# MUR_V0_1_Wiring.net
KiCad netlist of a schematic drawn in EAGLE
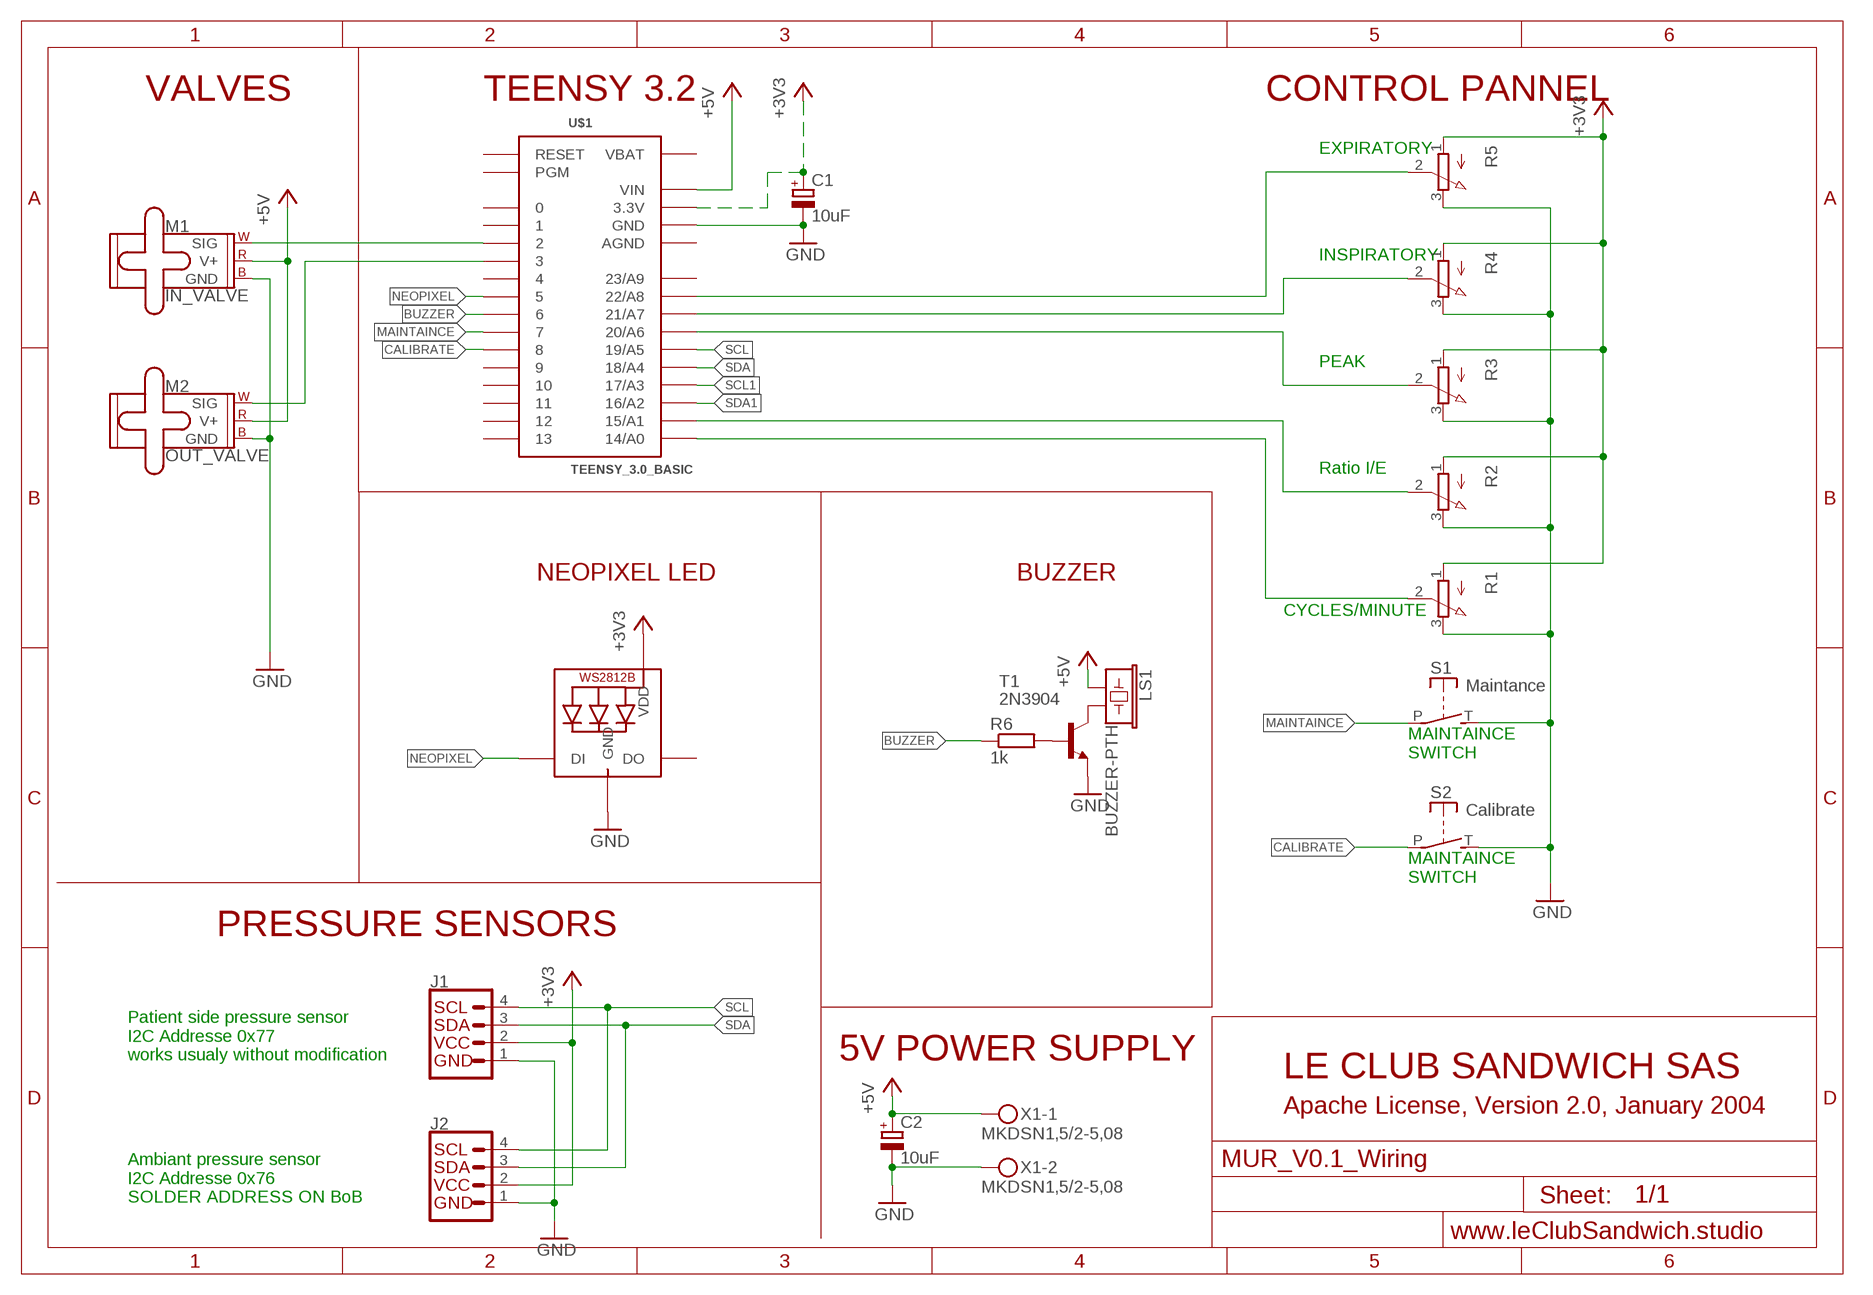
[diagram p0: schematic, sheet 1]

(export (version "E")
  (design (tool "Eeschema 10.0.6"))
  (components
    (comp (ref "C1")
      (value "10uF")
      (footprint "eagle-import:E2,5-6")
      (libsource (lib "eagle-import") (part "CPOL-EUE2.5-6"))
    )
    (comp (ref "C2")
      (value "10uF")
      (footprint "eagle-import:E2,5-6")
      (libsource (lib "eagle-import") (part "CPOL-EUE2.5-6"))
    )
    (comp (ref "J1")
      (value "I2C_STANDARD_NO_SILK")
      (footprint "eagle-import:1X04_NO_SILK")
      (libsource (lib "eagle-import") (part "I2C_STANDARD_NO_SILK"))
    )
    (comp (ref "J2")
      (value "I2C_STANDARD_NO_SILK")
      (footprint "eagle-import:1X04_NO_SILK")
      (libsource (lib "eagle-import") (part "I2C_STANDARD_NO_SILK"))
    )
    (comp (ref "LED1")
      (value "WS2812B5050")
      (footprint "eagle-import:WS2812B")
      (libsource (lib "eagle-import") (part "WS2812B5050"))
    )
    (comp (ref "LS1")
      (value "BUZZER-PTH")
      (footprint "eagle-import:BUZZER-12MM")
      (libsource (lib "eagle-import") (part "BUZZER-PTH"))
    )
    (comp (ref "M1")
      (value "IN_VALVE")
      (footprint "eagle-import:1X03")
      (libsource (lib "eagle-import") (part "SERVO"))
    )
    (comp (ref "M2")
      (value "OUT_VALVE")
      (footprint "eagle-import:1X03")
      (libsource (lib "eagle-import") (part "SERVO"))
    )
    (comp (ref "R1")
      (value "3RP/1610N")
      (footprint "eagle-import:3RP_1610N")
      (libsource (lib "eagle-import") (part "3RP/1610N"))
    )
    (comp (ref "R2")
      (value "3RP/1610N")
      (footprint "eagle-import:3RP_1610N")
      (libsource (lib "eagle-import") (part "3RP/1610N"))
    )
    (comp (ref "R3")
      (value "3RP/1610N")
      (footprint "eagle-import:3RP_1610N")
      (libsource (lib "eagle-import") (part "3RP/1610N"))
    )
    (comp (ref "R4")
      (value "3RP/1610N")
      (footprint "eagle-import:3RP_1610N")
      (libsource (lib "eagle-import") (part "3RP/1610N"))
    )
    (comp (ref "R5")
      (value "3RP/1610N")
      (footprint "eagle-import:3RP_1610N")
      (libsource (lib "eagle-import") (part "3RP/1610N"))
    )
    (comp (ref "R6")
      (value "1k")
      (footprint "eagle-import:0204_5")
      (libsource (lib "eagle-import") (part "R-EU_0204/5"))
    )
    (comp (ref "S1")
      (value "Maintance")
      (footprint "eagle-import:JUDCOSPST")
      (libsource (lib "eagle-import") (part "SPST"))
    )
    (comp (ref "S2")
      (value "Calibrate")
      (footprint "eagle-import:JUDCOSPST")
      (libsource (lib "eagle-import") (part "SPST"))
    )
    (comp (ref "T1")
      (value "2N3904")
      (footprint "eagle-import:TO92")
      (libsource (lib "eagle-import") (part "2N3904"))
    )
    (comp (ref "U$1")
      (value "TEENSY_3.0_BASIC")
      (footprint "eagle-import:TEENSY_3.0_BASIC")
      (libsource (lib "eagle-import") (part "TEENSY_3.0_BASIC"))
    )
    (comp (ref "X1")
      (value "MKDSN1,5/2-5,08")
      (footprint "eagle-import:MKDSN1,5_2-5,08")
      (libsource (lib "eagle-import") (part "MKDSN1,5/2-5,08"))
    )
  )
  (nets
    (net (code "1") (name "+3V3") (class "Default")
      (node (ref "C1") (pin "+") (pinfunction "+_+") (pintype "passive"))
      (node (ref "J1") (pin "2") (pinfunction "2_2") (pintype "power_in"))
      (node (ref "J2") (pin "2") (pinfunction "2_2") (pintype "power_in"))
      (node (ref "LED1") (pin "1-VDD") (pinfunction "VDD_1-VDD") (pintype "power_in"))
      (node (ref "R1") (pin "1") (pinfunction "A_1") (pintype "passive"))
      (node (ref "R2") (pin "1") (pinfunction "A_1") (pintype "passive"))
      (node (ref "R3") (pin "1") (pinfunction "A_1") (pintype "passive"))
      (node (ref "R4") (pin "1") (pinfunction "A_1") (pintype "passive"))
      (node (ref "R5") (pin "1") (pinfunction "A_1") (pintype "passive"))
      (node (ref "U$1") (pin "3.3V") (pinfunction "3.3V_3.3V") (pintype "power_in"))
      (node (ref "U$1") (pin "3.3V1") (pinfunction "3.3V_3.3V1") (pintype "power_in"))
    )
    (net (code "2") (name "+5V") (class "Default")
      (node (ref "C2") (pin "+") (pinfunction "+_+") (pintype "passive"))
      (node (ref "LS1") (pin "+") (pinfunction "1_+") (pintype "passive"))
      (node (ref "M1") (pin "2") (pinfunction "V+_2") (pintype "bidirectional"))
      (node (ref "M2") (pin "2") (pinfunction "V+_2") (pintype "bidirectional"))
      (node (ref "U$1") (pin "VIN") (pinfunction "VIN_VIN") (pintype "power_in"))
      (node (ref "X1") (pin "1") (pinfunction "KL_1") (pintype "passive"))
    )
    (net (code "3") (name "/AGND") (class "Default")
      (node (ref "U$1") (pin "AGND") (pinfunction "AGND_AGND") (pintype "power_in"))
    )
    (net (code "4") (name "/VBAT") (class "Default")
      (node (ref "U$1") (pin "VBAT") (pinfunction "VBAT_VBAT") (pintype "power_in"))
    )
    (net (code "5") (name "BUZZER") (class "Default")
      (node (ref "R6") (pin "1") (pinfunction "1_1") (pintype "passive"))
      (node (ref "U$1") (pin "6") (pinfunction "6_6") (pintype "bidirectional"))
    )
    (net (code "6") (name "CALIBRATE") (class "Default")
      (node (ref "S2") (pin "P") (pinfunction "P_P") (pintype "passive"))
      (node (ref "U$1") (pin "8") (pinfunction "8_8") (pintype "bidirectional"))
    )
    (net (code "7") (name "GND") (class "Default")
      (node (ref "C1") (pin "-") (pinfunction "-_-") (pintype "passive"))
      (node (ref "C2") (pin "-") (pinfunction "-_-") (pintype "passive"))
      (node (ref "J1") (pin "1") (pinfunction "1_1") (pintype "power_in"))
      (node (ref "J2") (pin "1") (pinfunction "1_1") (pintype "power_in"))
      (node (ref "LED1") (pin "3-GND") (pinfunction "GND_3-GND") (pintype "power_in"))
      (node (ref "M1") (pin "3") (pinfunction "GND_3") (pintype "bidirectional"))
      (node (ref "M2") (pin "3") (pinfunction "GND_3") (pintype "bidirectional"))
      (node (ref "R1") (pin "3") (pinfunction "E_3") (pintype "passive"))
      (node (ref "R2") (pin "3") (pinfunction "E_3") (pintype "passive"))
      (node (ref "R3") (pin "3") (pinfunction "E_3") (pintype "passive"))
      (node (ref "R4") (pin "3") (pinfunction "E_3") (pintype "passive"))
      (node (ref "R5") (pin "3") (pinfunction "E_3") (pintype "passive"))
      (node (ref "S1") (pin "T") (pinfunction "S_T") (pintype "passive"))
      (node (ref "S2") (pin "T") (pinfunction "S_T") (pintype "passive"))
      (node (ref "T1") (pin "3") (pinfunction "E_3") (pintype "passive"))
      (node (ref "U$1") (pin "GND") (pinfunction "GND_GND") (pintype "power_in"))
      (node (ref "U$1") (pin "GND1") (pinfunction "GND_GND1") (pintype "power_in"))
      (node (ref "X1") (pin "2") (pinfunction "KL_2") (pintype "passive"))
    )
    (net (code "8") (name "MAINTAINCE") (class "Default")
      (node (ref "S1") (pin "P") (pinfunction "P_P") (pintype "passive"))
      (node (ref "U$1") (pin "7") (pinfunction "7_7") (pintype "bidirectional"))
    )
    (net (code "9") (name "NEOPIXEL") (class "Default")
      (node (ref "LED1") (pin "4-DIN") (pinfunction "DI_4-DIN") (pintype "input"))
      (node (ref "U$1") (pin "5") (pinfunction "5_5") (pintype "bidirectional"))
    )
    (net (code "10") (name "Net-(LS1-2)") (class "Default")
      (node (ref "LS1") (pin "-") (pinfunction "2_-") (pintype "passive"))
      (node (ref "T1") (pin "1") (pinfunction "C_1") (pintype "passive"))
    )
    (net (code "11") (name "Net-(M1-SIG)") (class "Default")
      (node (ref "M1") (pin "1") (pinfunction "SIG_1") (pintype "bidirectional"))
      (node (ref "U$1") (pin "2") (pinfunction "2_2") (pintype "bidirectional"))
    )
    (net (code "12") (name "Net-(M2-SIG)") (class "Default")
      (node (ref "M2") (pin "1") (pinfunction "SIG_1") (pintype "bidirectional"))
      (node (ref "U$1") (pin "3") (pinfunction "3_3") (pintype "bidirectional"))
    )
    (net (code "13") (name "Net-(R1-S)") (class "Default")
      (node (ref "R1") (pin "2") (pinfunction "S_2") (pintype "passive"))
      (node (ref "U$1") (pin "14/A0") (pinfunction "14/A0_14/A0") (pintype "bidirectional"))
    )
    (net (code "14") (name "Net-(R2-S)") (class "Default")
      (node (ref "R2") (pin "2") (pinfunction "S_2") (pintype "passive"))
      (node (ref "U$1") (pin "15/A1") (pinfunction "15/A1_15/A1") (pintype "bidirectional"))
    )
    (net (code "15") (name "Net-(R3-S)") (class "Default")
      (node (ref "R3") (pin "2") (pinfunction "S_2") (pintype "passive"))
      (node (ref "U$1") (pin "20/A6") (pinfunction "20/A6_20/A6") (pintype "bidirectional"))
    )
    (net (code "16") (name "Net-(R4-S)") (class "Default")
      (node (ref "R4") (pin "2") (pinfunction "S_2") (pintype "passive"))
      (node (ref "U$1") (pin "21/A7") (pinfunction "21/A7_21/A7") (pintype "bidirectional"))
    )
    (net (code "17") (name "Net-(R5-S)") (class "Default")
      (node (ref "R5") (pin "2") (pinfunction "S_2") (pintype "passive"))
      (node (ref "U$1") (pin "22/A8") (pinfunction "22/A8_22/A8") (pintype "bidirectional"))
    )
    (net (code "18") (name "Net-(T1-B)") (class "Default")
      (node (ref "R6") (pin "2") (pinfunction "2_2") (pintype "passive"))
      (node (ref "T1") (pin "2") (pinfunction "B_2") (pintype "passive"))
    )
    (net (code "19") (name "SCL") (class "Default")
      (node (ref "J1") (pin "4") (pinfunction "4_4") (pintype "passive"))
      (node (ref "J2") (pin "4") (pinfunction "4_4") (pintype "passive"))
      (node (ref "U$1") (pin "19/A5") (pinfunction "19/A5_19/A5") (pintype "bidirectional"))
    )
    (net (code "20") (name "SCL1") (class "Default")
      (node (ref "U$1") (pin "17/A3") (pinfunction "17/A3_17/A3") (pintype "bidirectional"))
    )
    (net (code "21") (name "SDA") (class "Default")
      (node (ref "J1") (pin "3") (pinfunction "3_3") (pintype "passive"))
      (node (ref "J2") (pin "3") (pinfunction "3_3") (pintype "passive"))
      (node (ref "U$1") (pin "18/A4") (pinfunction "18/A4_18/A4") (pintype "bidirectional"))
    )
    (net (code "22") (name "SDA1") (class "Default")
      (node (ref "U$1") (pin "16/A2") (pinfunction "16/A2_16/A2") (pintype "bidirectional"))
    )
    (net (code "23") (name "unconnected-(LED1-DO-Pad2-DOUT)") (class "Default")
      (node (ref "LED1") (pin "2-DOUT") (pinfunction "DO_2-DOUT") (pintype "output"))
    )
    (net (code "24") (name "unconnected-(U$1-Pad0)") (class "Default")
      (node (ref "U$1") (pin "0") (pinfunction "0_0") (pintype "bidirectional"))
    )
    (net (code "25") (name "unconnected-(U$1-Pad1)") (class "Default")
      (node (ref "U$1") (pin "1") (pinfunction "1_1") (pintype "bidirectional"))
    )
    (net (code "26") (name "unconnected-(U$1-Pad4)") (class "Default")
      (node (ref "U$1") (pin "4") (pinfunction "4_4") (pintype "bidirectional"))
    )
    (net (code "27") (name "unconnected-(U$1-Pad9)") (class "Default")
      (node (ref "U$1") (pin "9") (pinfunction "9_9") (pintype "bidirectional"))
    )
    (net (code "28") (name "unconnected-(U$1-Pad10)") (class "Default")
      (node (ref "U$1") (pin "10") (pinfunction "10_10") (pintype "bidirectional"))
    )
    (net (code "29") (name "unconnected-(U$1-Pad11)") (class "Default")
      (node (ref "U$1") (pin "11") (pinfunction "11_11") (pintype "bidirectional"))
    )
    (net (code "30") (name "unconnected-(U$1-Pad12)") (class "Default")
      (node (ref "U$1") (pin "12") (pinfunction "12_12") (pintype "bidirectional"))
    )
    (net (code "31") (name "unconnected-(U$1-Pad13)") (class "Default")
      (node (ref "U$1") (pin "13") (pinfunction "13_13") (pintype "bidirectional"))
    )
    (net (code "32") (name "unconnected-(U$1-Pad23{slash}A9)") (class "Default")
      (node (ref "U$1") (pin "23/A9") (pinfunction "23/A9_23/A9") (pintype "bidirectional"))
    )
    (net (code "33") (name "unconnected-(U$1-PadPGM)") (class "Default")
      (node (ref "U$1") (pin "PGM") (pinfunction "PGM_PGM") (pintype "bidirectional"))
    )
    (net (code "34") (name "unconnected-(U$1-PadRESET)") (class "Default")
      (node (ref "U$1") (pin "RESET") (pinfunction "RESET_RESET") (pintype "bidirectional"))
    )
  )
)
